# ADJD-S311_Breakout.net
KiCad netlist of a schematic drawn in EAGLE
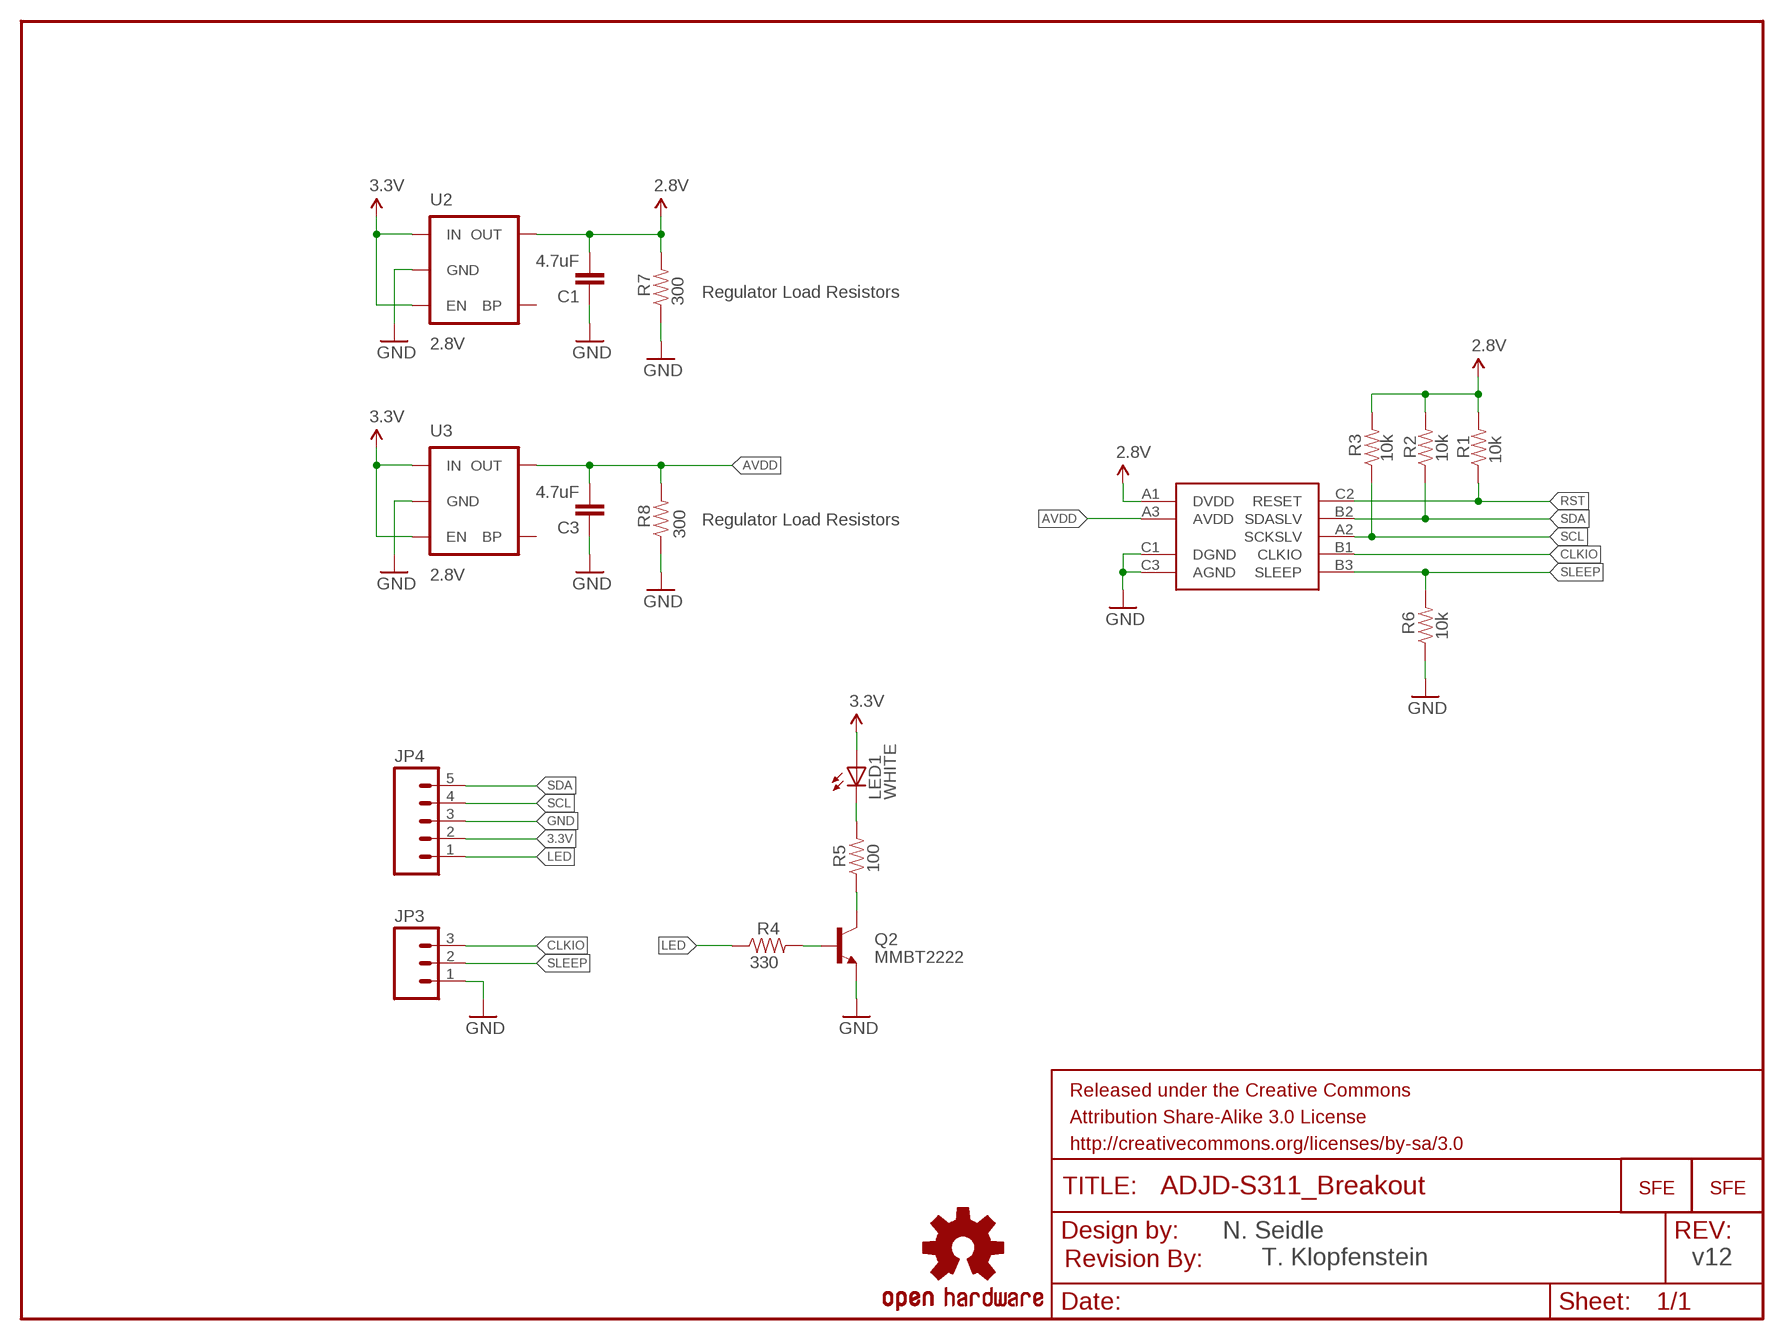
[diagram p0: schematic, sheet 1]

(export (version "E")
  (design (tool "Eeschema 10.0.6"))
  (components
    (comp (ref "C1")
      (value "4.7uF")
      (footprint "eagle-import:0603-CAP")
      (libsource (lib "eagle-import") (part "CAP0603-CAP"))
    )
    (comp (ref "C3")
      (value "4.7uF")
      (footprint "eagle-import:0603-CAP")
      (libsource (lib "eagle-import") (part "CAP0603-CAP"))
    )
    (comp (ref "FRAME1")
      (value "FRAME-LETTER")
      (footprint "eagle-import:CREATIVE_COMMONS")
      (libsource (lib "eagle-import") (part "FRAME-LETTER"))
    )
    (comp (ref "JP1")
      (value "LOGO-SFESK")
      (footprint "eagle-import:SFE-LOGO-FLAME")
      (libsource (lib "eagle-import") (part "LOGO-SFESK"))
    )
    (comp (ref "JP2")
      (value "LOGO-SFESK")
      (footprint "eagle-import:SFE-LOGO-FLAME")
      (libsource (lib "eagle-import") (part "LOGO-SFESK"))
    )
    (comp (ref "JP3")
      (value "M03PTH")
      (footprint "eagle-import:1X03")
      (libsource (lib "eagle-import") (part "M03PTH"))
    )
    (comp (ref "JP4")
      (value "M05PTH")
      (footprint "eagle-import:1X05")
      (libsource (lib "eagle-import") (part "M05PTH"))
    )
    (comp (ref "LED1")
      (value "WHITE")
      (footprint "eagle-import:LED-0603")
      (libsource (lib "eagle-import") (part "LED0603"))
    )
    (comp (ref "Q2")
      (value "MMBT2222")
      (footprint "eagle-import:SOT23-3")
      (libsource (lib "eagle-import") (part "TRANSISTOR_NPNSOT23-3"))
    )
    (comp (ref "R1")
      (value "10k")
      (footprint "eagle-import:0603-RES")
      (libsource (lib "eagle-import") (part "RESISTOR0603-RES"))
    )
    (comp (ref "R2")
      (value "10k")
      (footprint "eagle-import:0603-RES")
      (libsource (lib "eagle-import") (part "RESISTOR0603-RES"))
    )
    (comp (ref "R3")
      (value "10k")
      (footprint "eagle-import:0603-RES")
      (libsource (lib "eagle-import") (part "RESISTOR0603-RES"))
    )
    (comp (ref "R4")
      (value "330")
      (footprint "eagle-import:0603-RES")
      (libsource (lib "eagle-import") (part "RESISTOR0603-RES"))
    )
    (comp (ref "R5")
      (value "100")
      (footprint "eagle-import:0603-RES")
      (libsource (lib "eagle-import") (part "RESISTOR0603-RES"))
    )
    (comp (ref "R6")
      (value "10k")
      (footprint "eagle-import:0603-RES")
      (libsource (lib "eagle-import") (part "RESISTOR0603-RES"))
    )
    (comp (ref "R7")
      (value "300")
      (footprint "eagle-import:0603-RES")
      (libsource (lib "eagle-import") (part "RESISTOR0603-RES"))
    )
    (comp (ref "R8")
      (value "300")
      (footprint "eagle-import:0603-RES")
      (libsource (lib "eagle-import") (part "RESISTOR0603-RES"))
    )
    (comp (ref "U$1")
      (value "REVISION")
      (footprint "eagle-import:REVISION")
      (libsource (lib "eagle-import") (part "REVISION"))
    )
    (comp (ref "U$4")
      (value "OSHW-LOGOS")
      (footprint "eagle-import:OSHW-LOGO-S")
      (libsource (lib "eagle-import") (part "OSHW-LOGOS"))
    )
    (comp (ref "U1")
      (value "ADJD-S311-CR999")
      (footprint "eagle-import:CSP-9")
      (libsource (lib "eagle-import") (part "ADJD-S311-CR999"))
    )
    (comp (ref "U2")
      (value "2.8V")
      (footprint "eagle-import:SOT23-5")
      (libsource (lib "eagle-import") (part "V_REG_LDOSMD"))
    )
    (comp (ref "U3")
      (value "2.8V")
      (footprint "eagle-import:SOT23-5")
      (libsource (lib "eagle-import") (part "V_REG_LDOSMD"))
    )
  )
  (nets
    (net (code "1") (name "2.8V") (class "Default")
      (node (ref "C1") (pin "2") (pinfunction "2_2") (pintype "passive"))
      (node (ref "R1") (pin "2") (pinfunction "2_2") (pintype "passive"))
      (node (ref "R2") (pin "2") (pinfunction "2_2") (pintype "passive"))
      (node (ref "R3") (pin "2") (pinfunction "2_2") (pintype "passive"))
      (node (ref "R7") (pin "2") (pinfunction "2_2") (pintype "passive"))
      (node (ref "U1") (pin "A1") (pinfunction "DVDD_A1") (pintype "bidirectional"))
      (node (ref "U2") (pin "5") (pinfunction "OUT_5") (pintype "passive"))
    )
    (net (code "2") (name "3.3V") (class "Default")
      (node (ref "JP4") (pin "2") (pinfunction "2_2") (pintype "passive"))
      (node (ref "LED1") (pin "A") (pinfunction "A_A") (pintype "passive"))
      (node (ref "U2") (pin "1") (pinfunction "IN_1") (pintype "input"))
      (node (ref "U2") (pin "3") (pinfunction "EN_3") (pintype "input"))
      (node (ref "U3") (pin "1") (pinfunction "IN_1") (pintype "input"))
      (node (ref "U3") (pin "3") (pinfunction "EN_3") (pintype "input"))
    )
    (net (code "3") (name "AVDD") (class "Default")
      (node (ref "C3") (pin "2") (pinfunction "2_2") (pintype "passive"))
      (node (ref "R8") (pin "2") (pinfunction "2_2") (pintype "passive"))
      (node (ref "U1") (pin "A3") (pinfunction "AVDD_A3") (pintype "bidirectional"))
      (node (ref "U3") (pin "5") (pinfunction "OUT_5") (pintype "passive"))
    )
    (net (code "4") (name "CLKIO") (class "Default")
      (node (ref "JP3") (pin "3") (pinfunction "3_3") (pintype "passive"))
      (node (ref "U1") (pin "B1") (pinfunction "CLKIO_B1") (pintype "bidirectional"))
    )
    (net (code "5") (name "GND") (class "Default")
      (node (ref "C1") (pin "1") (pinfunction "1_1") (pintype "passive"))
      (node (ref "C3") (pin "1") (pinfunction "1_1") (pintype "passive"))
      (node (ref "JP3") (pin "1") (pinfunction "1_1") (pintype "passive"))
      (node (ref "JP4") (pin "3") (pinfunction "3_3") (pintype "passive"))
      (node (ref "Q2") (pin "2") (pinfunction "E_2") (pintype "passive"))
      (node (ref "R6") (pin "1") (pinfunction "1_1") (pintype "passive"))
      (node (ref "R7") (pin "1") (pinfunction "1_1") (pintype "passive"))
      (node (ref "R8") (pin "1") (pinfunction "1_1") (pintype "passive"))
      (node (ref "U1") (pin "C1") (pinfunction "DGND_C1") (pintype "bidirectional"))
      (node (ref "U1") (pin "C3") (pinfunction "AGND_C3") (pintype "bidirectional"))
      (node (ref "U2") (pin "2") (pinfunction "GND_2") (pintype "input"))
      (node (ref "U3") (pin "2") (pinfunction "GND_2") (pintype "input"))
    )
    (net (code "6") (name "LED") (class "Default")
      (node (ref "JP4") (pin "1") (pinfunction "1_1") (pintype "passive"))
      (node (ref "R4") (pin "1") (pinfunction "1_1") (pintype "passive"))
    )
    (net (code "7") (name "Net-(LED1-PadC)") (class "Default")
      (node (ref "LED1") (pin "C") (pinfunction "C_C") (pintype "passive"))
      (node (ref "R5") (pin "2") (pinfunction "2_2") (pintype "passive"))
    )
    (net (code "8") (name "Net-(Q2-B)") (class "Default")
      (node (ref "Q2") (pin "1") (pinfunction "B_1") (pintype "passive"))
      (node (ref "R4") (pin "2") (pinfunction "2_2") (pintype "passive"))
    )
    (net (code "9") (name "Net-(Q2-C)") (class "Default")
      (node (ref "Q2") (pin "3") (pinfunction "C_3") (pintype "passive"))
      (node (ref "R5") (pin "1") (pinfunction "1_1") (pintype "passive"))
    )
    (net (code "10") (name "RST") (class "Default")
      (node (ref "R1") (pin "1") (pinfunction "1_1") (pintype "passive"))
      (node (ref "U1") (pin "C2") (pinfunction "RESET_C2") (pintype "bidirectional"))
    )
    (net (code "11") (name "SCL") (class "Default")
      (node (ref "JP4") (pin "4") (pinfunction "4_4") (pintype "passive"))
      (node (ref "R3") (pin "1") (pinfunction "1_1") (pintype "passive"))
      (node (ref "U1") (pin "A2") (pinfunction "SCKSLV_A2") (pintype "bidirectional"))
    )
    (net (code "12") (name "SDA") (class "Default")
      (node (ref "JP4") (pin "5") (pinfunction "5_5") (pintype "passive"))
      (node (ref "R2") (pin "1") (pinfunction "1_1") (pintype "passive"))
      (node (ref "U1") (pin "B2") (pinfunction "SDASLV_B2") (pintype "bidirectional"))
    )
    (net (code "13") (name "SLEEP") (class "Default")
      (node (ref "JP3") (pin "2") (pinfunction "2_2") (pintype "passive"))
      (node (ref "R6") (pin "2") (pinfunction "2_2") (pintype "passive"))
      (node (ref "U1") (pin "B3") (pinfunction "SLEEP_B3") (pintype "bidirectional"))
    )
    (net (code "14") (name "unconnected-(U2-BP-Pad4)") (class "Default")
      (node (ref "U2") (pin "4") (pinfunction "BP_4") (pintype "input"))
    )
    (net (code "15") (name "unconnected-(U3-BP-Pad4)") (class "Default")
      (node (ref "U3") (pin "4") (pinfunction "BP_4") (pintype "input"))
    )
  )
)
